# 684-plant-watering.net
KiCad netlist of a schematic drawn in EAGLE
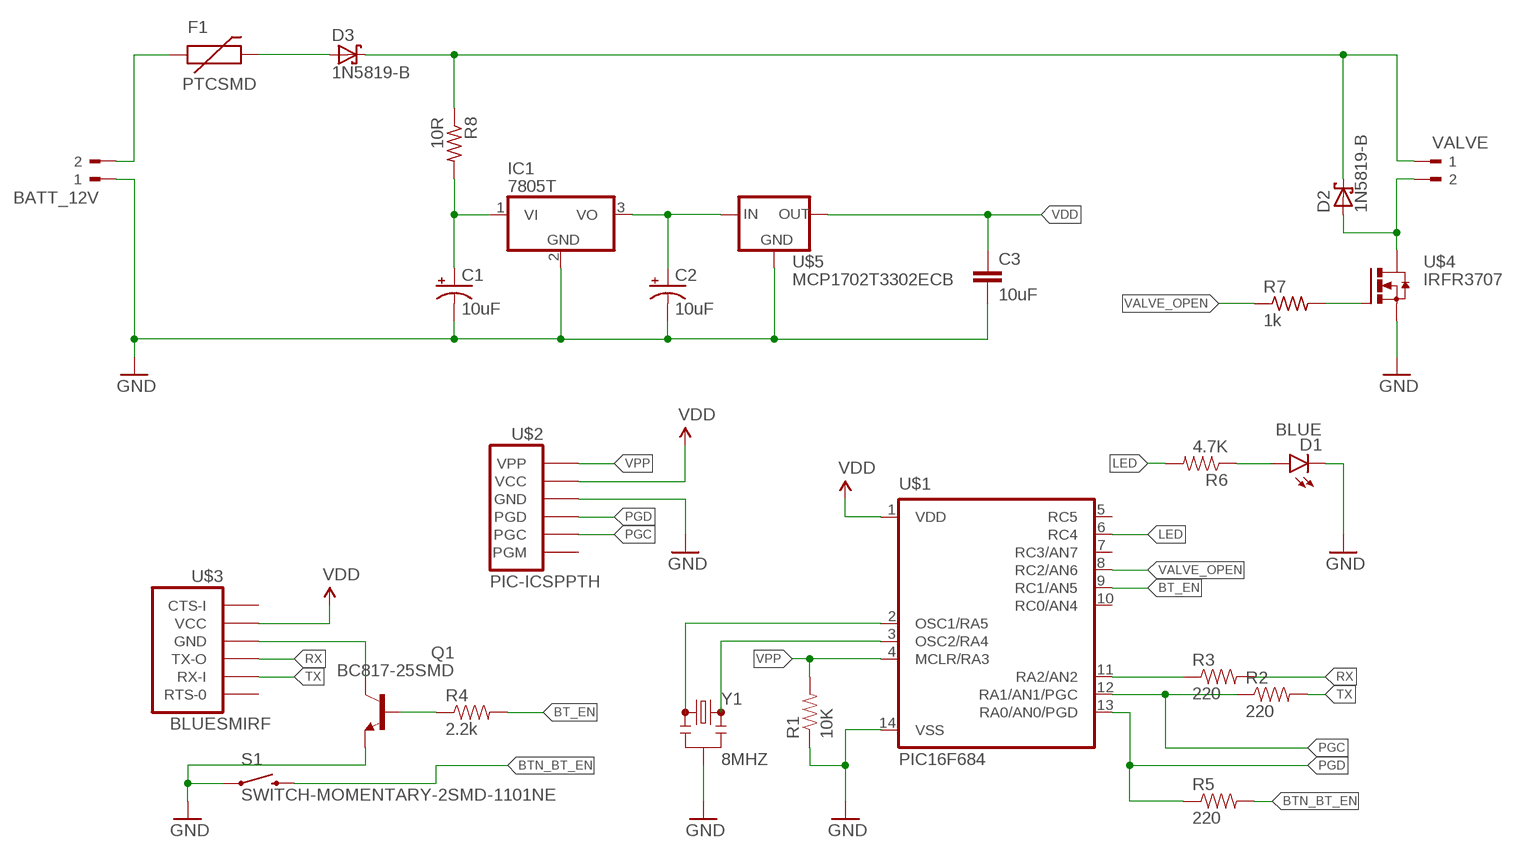
[diagram p0: schematic, sheet 1]

(export (version "E")
  (design (tool "Eeschema 10.0.6"))
  (components
    (comp (ref "BATT_12V")
      (value "180-2")
      (footprint "eagle-import:180-2")
      (libsource (lib "eagle-import") (part "180-2"))
    )
    (comp (ref "C1")
      (value "10uF")
      (footprint "eagle-import:CPOL-RADIAL-10UF-25V")
      (libsource (lib "eagle-import") (part "10UF-25V-20%(PTH)"))
    )
    (comp (ref "C2")
      (value "10uF")
      (footprint "eagle-import:CPOL-RADIAL-10UF-25V")
      (libsource (lib "eagle-import") (part "10UF-25V-20%(PTH)"))
    )
    (comp (ref "C3")
      (value "10uF")
      (footprint "eagle-import:0603-CAP")
      (libsource (lib "eagle-import") (part "10UF-6.3V-20%(0603)"))
    )
    (comp (ref "D1")
      (value "BLUE")
      (footprint "eagle-import:LED-1206")
      (libsource (lib "eagle-import") (part "LED-BLUE1206"))
    )
    (comp (ref "D2")
      (value "1N5819-B")
      (footprint "eagle-import:DO41-7.6")
      (libsource (lib "eagle-import") (part "1N5819-B"))
    )
    (comp (ref "D3")
      (value "1N5819-B")
      (footprint "eagle-import:DO41-7.6")
      (libsource (lib "eagle-import") (part "1N5819-B"))
    )
    (comp (ref "F1")
      (value "PTCSMD")
      (footprint "eagle-import:PTC-1206")
      (libsource (lib "eagle-import") (part "PTCSMD"))
    )
    (comp (ref "IC1")
      (value "7805T")
      (footprint "eagle-import:TO220H")
      (libsource (lib "eagle-import") (part "78T05"))
    )
    (comp (ref "Q1")
      (value "BC817-25SMD")
      (footprint "eagle-import:SOT23-BEC")
      (libsource (lib "eagle-import") (part "BC817SMD-25"))
    )
    (comp (ref "R1")
      (value "10K")
      (footprint "eagle-import:0603-RES")
      (libsource (lib "eagle-import") (part "10KOHM-1/10W-1%(0603)0603"))
    )
    (comp (ref "R2")
      (value "220")
      (footprint "eagle-import:0603-RES")
      (libsource (lib "eagle-import") (part "220OHM-1/10W-1%(0603)"))
    )
    (comp (ref "R3")
      (value "220")
      (footprint "eagle-import:0603-RES")
      (libsource (lib "eagle-import") (part "220OHM-1/10W-1%(0603)"))
    )
    (comp (ref "R4")
      (value "2.2k")
      (footprint "eagle-import:0603-RES")
      (libsource (lib "eagle-import") (part "2.2KOHM-1/10W-1%(0603)"))
    )
    (comp (ref "R5")
      (value "220")
      (footprint "eagle-import:0603-RES")
      (libsource (lib "eagle-import") (part "220OHM-1/10W-1%(0603)"))
    )
    (comp (ref "R6")
      (value "4.7K")
      (footprint "eagle-import:0603-RES")
      (libsource (lib "eagle-import") (part "4.7KOHM-1/10W-1%(0603)"))
    )
    (comp (ref "R7")
      (value "1k")
      (footprint "eagle-import:0207_10")
      (libsource (lib "eagle-import") (part "resistor_R-US_0207/10"))
    )
    (comp (ref "R8")
      (value "10R")
      (footprint "eagle-import:0309_12")
      (libsource (lib "eagle-import") (part "R-US_0309/12"))
    )
    (comp (ref "S1")
      (value "SWITCH-MOMENTARY-2SMD-1101NE")
      (footprint "eagle-import:TACTILE-SWITCH-1101NE")
      (libsource (lib "eagle-import") (part "SWITCH-MOMENTARY-2SMD-1101NE"))
    )
    (comp (ref "U$1")
      (value "PIC16F684")
      (footprint "eagle-import:SO14")
      (libsource (lib "eagle-import") (part "PIC16F684"))
    )
    (comp (ref "U$2")
      (value "PIC-ICSPPTH")
      (footprint "eagle-import:MOLEX-1X6")
      (libsource (lib "eagle-import") (part "PIC-ICSPPTH"))
    )
    (comp (ref "U$3")
      (value "BLUESMIRF")
      (footprint "eagle-import:1X06")
      (libsource (lib "eagle-import") (part "BLUESMIRF"))
    )
    (comp (ref "U$4")
      (value "IRFR3707")
      (footprint "eagle-import:TO252")
      (libsource (lib "eagle-import") (part "IRFR3707"))
    )
    (comp (ref "U$5")
      (value "MCP1702T3302ECB")
      (footprint "eagle-import:SOT23")
      (libsource (lib "eagle-import") (part "MCP1702T3302ECB"))
    )
    (comp (ref "VALVE")
      (value "180-2")
      (footprint "eagle-import:180-2")
      (libsource (lib "eagle-import") (part "180-2"))
    )
    (comp (ref "Y1")
      (value "8MHZ")
      (footprint "eagle-import:RESONATOR-SMD")
      (libsource (lib "eagle-import") (part "RESONATOR8MHZ"))
    )
  )
  (nets
    (net (code "1") (name "BTN_BT_EN") (class "Default")
      (node (ref "R5") (pin "2") (pinfunction "2_2") (pintype "passive"))
      (node (ref "S1") (pin "2") (pinfunction "2_2") (pintype "passive"))
    )
    (net (code "2") (name "BT_EN") (class "Default")
      (node (ref "R4") (pin "2") (pinfunction "2_2") (pintype "passive"))
      (node (ref "U$1") (pin "9") (pinfunction "RC1/AN5_9") (pintype "bidirectional"))
    )
    (net (code "3") (name "GND") (class "Default")
      (node (ref "BATT_12V") (pin "1") (pinfunction "1_1") (pintype "passive"))
      (node (ref "C1") (pin "2") (pinfunction "-_2") (pintype "passive"))
      (node (ref "C2") (pin "2") (pinfunction "-_2") (pintype "passive"))
      (node (ref "C3") (pin "2") (pinfunction "2_2") (pintype "passive"))
      (node (ref "D1") (pin "C") (pinfunction "C_C") (pintype "passive"))
      (node (ref "IC1") (pin "2") (pinfunction "GND_2") (pintype "passive"))
      (node (ref "Q1") (pin "E") (pinfunction "E_E") (pintype "passive"))
      (node (ref "R1") (pin "1") (pinfunction "1_1") (pintype "passive"))
      (node (ref "S1") (pin "1") (pinfunction "1_1") (pintype "passive"))
      (node (ref "U$1") (pin "14") (pinfunction "VSS_14") (pintype "power_in"))
      (node (ref "U$2") (pin "4") (pinfunction "GND_4") (pintype "bidirectional"))
      (node (ref "U$4") (pin "3") (pinfunction "S_3") (pintype "passive"))
      (node (ref "U$5") (pin "1") (pinfunction "GND_1") (pintype "input"))
      (node (ref "Y1") (pin "2") (pinfunction "2_2") (pintype "passive"))
    )
    (net (code "4") (name "LED") (class "Default")
      (node (ref "R6") (pin "2") (pinfunction "2_2") (pintype "passive"))
      (node (ref "U$1") (pin "6") (pinfunction "RC4_6") (pintype "bidirectional"))
    )
    (net (code "5") (name "Net-(BATT_12V-Pad2)") (class "Default")
      (node (ref "BATT_12V") (pin "2") (pinfunction "2_2") (pintype "passive"))
      (node (ref "F1") (pin "1") (pinfunction "1_1") (pintype "bidirectional"))
    )
    (net (code "6") (name "Net-(C1-+)") (class "Default")
      (node (ref "C1") (pin "1") (pinfunction "+_1") (pintype "passive"))
      (node (ref "IC1") (pin "1") (pinfunction "VI_1") (pintype "input"))
      (node (ref "R8") (pin "2") (pinfunction "2_2") (pintype "passive"))
    )
    (net (code "7") (name "Net-(C2-+)") (class "Default")
      (node (ref "C2") (pin "1") (pinfunction "+_1") (pintype "passive"))
      (node (ref "IC1") (pin "3") (pinfunction "VO_3") (pintype "passive"))
      (node (ref "U$5") (pin "3") (pinfunction "IN_3") (pintype "input"))
    )
    (net (code "8") (name "Net-(D1-PadA)") (class "Default")
      (node (ref "D1") (pin "A") (pinfunction "A_A") (pintype "passive"))
      (node (ref "R6") (pin "1") (pinfunction "1_1") (pintype "passive"))
    )
    (net (code "9") (name "Net-(D2-PadC)") (class "Default")
      (node (ref "D2") (pin "C") (pinfunction "C_C") (pintype "passive"))
      (node (ref "D3") (pin "C") (pinfunction "C_C") (pintype "passive"))
      (node (ref "R8") (pin "1") (pinfunction "1_1") (pintype "passive"))
      (node (ref "VALVE") (pin "1") (pinfunction "1_1") (pintype "passive"))
    )
    (net (code "10") (name "Net-(D3-PadA)") (class "Default")
      (node (ref "D3") (pin "A") (pinfunction "A_A") (pintype "passive"))
      (node (ref "F1") (pin "2") (pinfunction "2_2") (pintype "bidirectional"))
    )
    (net (code "11") (name "Net-(Q1-PadB)") (class "Default")
      (node (ref "Q1") (pin "B") (pinfunction "B_B") (pintype "passive"))
      (node (ref "R4") (pin "1") (pinfunction "1_1") (pintype "passive"))
    )
    (net (code "12") (name "Net-(U$1-OSC1{slash}RA5)") (class "Default")
      (node (ref "U$1") (pin "2") (pinfunction "OSC1/RA5_2") (pintype "input"))
      (node (ref "Y1") (pin "1") (pinfunction "1_1") (pintype "passive"))
    )
    (net (code "13") (name "Net-(U$1-OSC2{slash}RA4)") (class "Default")
      (node (ref "U$1") (pin "3") (pinfunction "OSC2/RA4_3") (pintype "output"))
      (node (ref "Y1") (pin "3") (pinfunction "3_3") (pintype "passive"))
    )
    (net (code "14") (name "Net-(U$1-RA2{slash}AN2)") (class "Default")
      (node (ref "R3") (pin "1") (pinfunction "1_1") (pintype "passive"))
      (node (ref "U$1") (pin "11") (pinfunction "RA2/AN2_11") (pintype "bidirectional"))
    )
    (net (code "15") (name "Net-(U$3-GND)") (class "Default")
      (node (ref "Q1") (pin "C") (pinfunction "C_C") (pintype "passive"))
      (node (ref "U$3") (pin "3") (pinfunction "GND_3") (pintype "bidirectional"))
    )
    (net (code "16") (name "Net-(U$4-D)") (class "Default")
      (node (ref "D2") (pin "A") (pinfunction "A_A") (pintype "passive"))
      (node (ref "U$4") (pin "4") (pinfunction "D_4") (pintype "passive"))
      (node (ref "VALVE") (pin "2") (pinfunction "2_2") (pintype "passive"))
    )
    (net (code "17") (name "Net-(U$4-G)") (class "Default")
      (node (ref "R7") (pin "2") (pinfunction "2_2") (pintype "passive"))
      (node (ref "U$4") (pin "1") (pinfunction "G_1") (pintype "passive"))
    )
    (net (code "18") (name "PGC") (class "Default")
      (node (ref "R2") (pin "1") (pinfunction "1_1") (pintype "passive"))
      (node (ref "U$1") (pin "12") (pinfunction "RA1/AN1/PGC_12") (pintype "bidirectional"))
      (node (ref "U$2") (pin "2") (pinfunction "PGC_2") (pintype "bidirectional"))
    )
    (net (code "19") (name "PGD") (class "Default")
      (node (ref "R5") (pin "1") (pinfunction "1_1") (pintype "passive"))
      (node (ref "U$1") (pin "13") (pinfunction "RA0/AN0/PGD_13") (pintype "bidirectional"))
      (node (ref "U$2") (pin "3") (pinfunction "PGD_3") (pintype "bidirectional"))
    )
    (net (code "20") (name "RX") (class "Default")
      (node (ref "R3") (pin "2") (pinfunction "2_2") (pintype "passive"))
      (node (ref "U$3") (pin "4") (pinfunction "TX-O_4") (pintype "bidirectional"))
    )
    (net (code "21") (name "TX") (class "Default")
      (node (ref "R2") (pin "2") (pinfunction "2_2") (pintype "passive"))
      (node (ref "U$3") (pin "5") (pinfunction "RX-I_5") (pintype "bidirectional"))
    )
    (net (code "22") (name "VALVE_OPEN") (class "Default")
      (node (ref "R7") (pin "1") (pinfunction "1_1") (pintype "passive"))
      (node (ref "U$1") (pin "8") (pinfunction "RC2/AN6_8") (pintype "bidirectional"))
    )
    (net (code "23") (name "VDD") (class "Default")
      (node (ref "C3") (pin "1") (pinfunction "1_1") (pintype "passive"))
      (node (ref "U$1") (pin "1") (pinfunction "VDD_1") (pintype "power_in"))
      (node (ref "U$2") (pin "5") (pinfunction "VCC_5") (pintype "bidirectional"))
      (node (ref "U$3") (pin "2") (pinfunction "VCC_2") (pintype "bidirectional"))
      (node (ref "U$5") (pin "2") (pinfunction "OUT_2") (pintype "passive"))
    )
    (net (code "24") (name "VPP") (class "Default")
      (node (ref "R1") (pin "2") (pinfunction "2_2") (pintype "passive"))
      (node (ref "U$1") (pin "4") (pinfunction "MCLR/RA3_4") (pintype "input"))
      (node (ref "U$2") (pin "6") (pinfunction "VPP_6") (pintype "bidirectional"))
    )
    (net (code "25") (name "unconnected-(U$1-RC0{slash}AN4-Pad10)") (class "Default")
      (node (ref "U$1") (pin "10") (pinfunction "RC0/AN4_10") (pintype "bidirectional"))
    )
    (net (code "26") (name "unconnected-(U$1-RC3{slash}AN7-Pad7)") (class "Default")
      (node (ref "U$1") (pin "7") (pinfunction "RC3/AN7_7") (pintype "bidirectional"))
    )
    (net (code "27") (name "unconnected-(U$1-RC5-Pad5)") (class "Default")
      (node (ref "U$1") (pin "5") (pinfunction "RC5_5") (pintype "bidirectional"))
    )
    (net (code "28") (name "unconnected-(U$2-PGM-Pad1)") (class "Default")
      (node (ref "U$2") (pin "1") (pinfunction "PGM_1") (pintype "bidirectional"))
    )
    (net (code "29") (name "unconnected-(U$3-CTS-I-Pad1)") (class "Default")
      (node (ref "U$3") (pin "1") (pinfunction "CTS-I_1") (pintype "bidirectional"))
    )
    (net (code "30") (name "unconnected-(U$3-RTS-0-Pad6)") (class "Default")
      (node (ref "U$3") (pin "6") (pinfunction "RTS-0_6") (pintype "bidirectional"))
    )
  )
)
